# BLE_Connectivity.net
KiCad netlist of a schematic drawn in Altium Designer
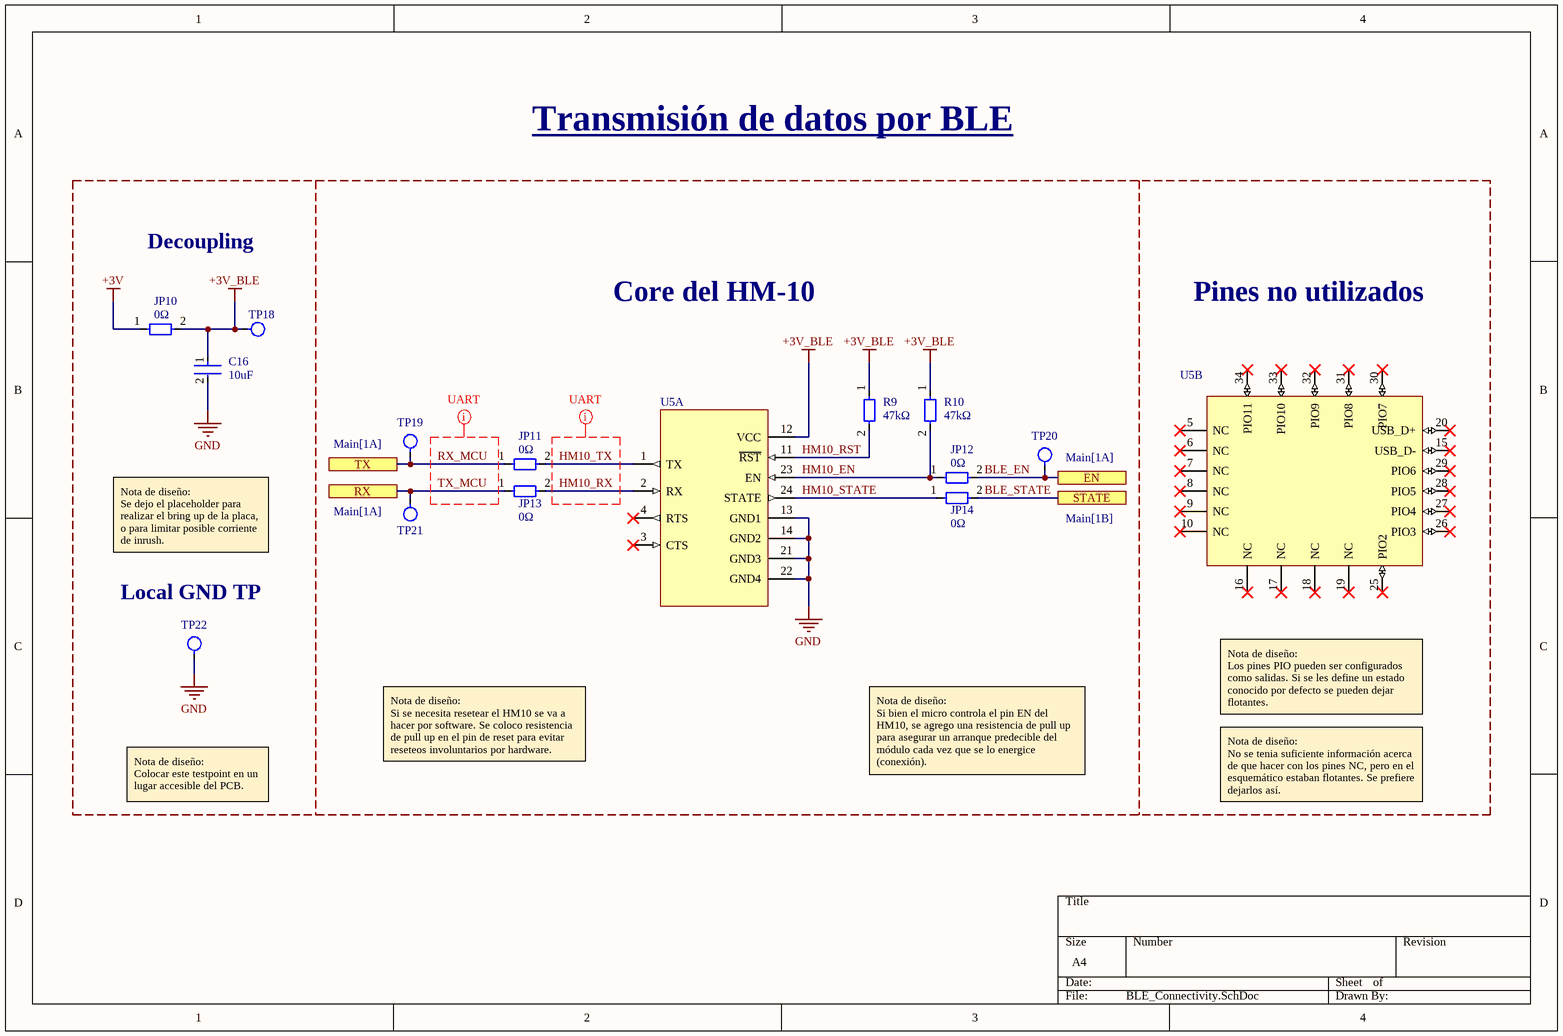
[diagram p0: BLE_Connectivity.SchDoc]

(export (version "E")
  (design (tool "Eeschema 10.0.6"))
  (components
    (comp (ref "C16")
      (value "10uF")
      (footprint "CAP_0603")
      (description "Cap 10 uF 10V X7R 0603")
      (fields (field (name "CAPACITANCE") "10uF") (field (name "TOLERANCE") "10%"))
      (libsource (lib "Passive_Components") (part "Generic C"))
    )
    (comp (ref "JP10")
      (value "0Ω")
      (footprint "RES_0R_0603")
      (description "Simbolo de jumper genérico")
      (fields (field (name "Comment") "Generic JP"))
      (libsource (lib "Passive_Components") (part "Generic JP"))
    )
    (comp (ref "JP11")
      (value "0Ω")
      (footprint "RES_0R_0603")
      (description "Simbolo de jumper genérico")
      (fields (field (name "Comment") "Generic JP"))
      (libsource (lib "Passive_Components") (part "Generic JP"))
    )
    (comp (ref "JP12")
      (value "0Ω")
      (footprint "RES_0R_0603")
      (description "Simbolo de jumper genérico")
      (fields (field (name "Comment") "Generic JP"))
      (libsource (lib "Passive_Components") (part "Generic JP"))
    )
    (comp (ref "JP13")
      (value "0Ω")
      (footprint "RES_0R_0603")
      (description "Simbolo de jumper genérico")
      (fields (field (name "Comment") "Generic JP"))
      (libsource (lib "Passive_Components") (part "Generic JP"))
    )
    (comp (ref "JP14")
      (value "0Ω")
      (footprint "RES_0R_0603")
      (description "Simbolo de jumper genérico")
      (fields (field (name "Comment") "Generic JP"))
      (libsource (lib "Passive_Components") (part "Generic JP"))
    )
    (comp (ref "R9")
      (value "47kΩ")
      (footprint "RES_0603")
      (description "RES  47k 1% 0603")
      (fields (field (name "Comment") "47k"))
      (libsource (lib "Passive_Components") (part "Generic R"))
    )
    (comp (ref "R10")
      (value "47kΩ")
      (footprint "RES_0603")
      (description "RES  47k 1% 0603")
      (fields (field (name "Comment") "47k"))
      (libsource (lib "Passive_Components") (part "Generic R"))
    )
    (comp (ref "TP18")
      (value "Testpoint SMD")
      (footprint "Testpoint_SMD")
      (description "Testpoint SMD de 1mm de diametro.")
      (libsource (lib "Connectors") (part "Testpoint_SMD"))
    )
    (comp (ref "TP19")
      (value "Testpoint SMD")
      (footprint "Testpoint_SMD")
      (description "Testpoint SMD de 1mm de diametro.")
      (libsource (lib "Connectors") (part "Testpoint_SMD"))
    )
    (comp (ref "TP20")
      (value "Testpoint SMD")
      (footprint "Testpoint_SMD")
      (description "Testpoint SMD de 1mm de diametro.")
      (libsource (lib "Connectors") (part "Testpoint_SMD"))
    )
    (comp (ref "TP21")
      (value "Testpoint SMD")
      (footprint "Testpoint_SMD")
      (description "Testpoint SMD de 1mm de diametro.")
      (libsource (lib "Connectors") (part "Testpoint_SMD"))
    )
    (comp (ref "TP22")
      (value "Testpoint SMD")
      (footprint "Testpoint_SMD")
      (description "Testpoint SMD de 1mm de diametro.")
      (libsource (lib "Connectors") (part "Testpoint_SMD"))
    )
    (comp (ref "U5")
      (value "HM10 BLE Module")
      (footprint "HM10_FOOTPRINT")
      (description "Modulo BLE HM10 con castellated pads.")
      (libsource (lib "Connectivity") (part "HM10"))
    )
  )
  (nets
    (net (code "1") (name "+3V") (class "Default")
      (node (ref "JP10") (pin "1") (pinfunction "1_1") (pintype "passive"))
    )
    (net (code "2") (name "+3V_BLE") (class "Default")
      (node (ref "C16") (pin "1") (pinfunction "1_1") (pintype "passive"))
      (node (ref "JP10") (pin "2") (pinfunction "2_2") (pintype "passive"))
      (node (ref "R10") (pin "1") (pinfunction "1_1") (pintype "passive"))
      (node (ref "R9") (pin "1") (pinfunction "1_1") (pintype "passive"))
      (node (ref "TP18") (pin "1") (pinfunction "1_1") (pintype "passive"))
      (node (ref "U5") (pin "12") (pinfunction "VCC_12") (pintype "power_in"))
    )
    (net (code "3") (name "/BLE_EN") (class "Default")
      (node (ref "JP12") (pin "2") (pinfunction "2_2") (pintype "passive"))
      (node (ref "TP20") (pin "1") (pinfunction "1_1") (pintype "passive"))
    )
    (net (code "4") (name "/BLE_STATE") (class "Default")
      (node (ref "JP14") (pin "2") (pinfunction "2_2") (pintype "passive"))
    )
    (net (code "5") (name "/HM10_EN") (class "Default")
      (node (ref "JP12") (pin "1") (pinfunction "1_1") (pintype "passive"))
      (node (ref "R10") (pin "2") (pinfunction "2_2") (pintype "passive"))
      (node (ref "U5") (pin "23") (pinfunction "EN_23") (pintype "input"))
    )
    (net (code "6") (name "/HM10_RST") (class "Default")
      (node (ref "R9") (pin "2") (pinfunction "2_2") (pintype "passive"))
      (node (ref "U5") (pin "11") (pinfunction "RST_11") (pintype "input"))
    )
    (net (code "7") (name "/HM10_RX") (class "Default")
      (node (ref "JP13") (pin "2") (pinfunction "2_2") (pintype "passive"))
      (node (ref "U5") (pin "2") (pinfunction "RX_2") (pintype "input"))
    )
    (net (code "8") (name "/HM10_STATE") (class "Default")
      (node (ref "JP14") (pin "1") (pinfunction "1_1") (pintype "passive"))
      (node (ref "U5") (pin "24") (pinfunction "STATE_24") (pintype "output"))
    )
    (net (code "9") (name "/HM10_TX") (class "Default")
      (node (ref "JP11") (pin "2") (pinfunction "2_2") (pintype "passive"))
      (node (ref "U5") (pin "1") (pinfunction "TX_1") (pintype "output"))
    )
    (net (code "10") (name "/RX_MCU") (class "Default")
      (node (ref "JP11") (pin "1") (pinfunction "1_1") (pintype "passive"))
      (node (ref "TP19") (pin "1") (pinfunction "1_1") (pintype "passive"))
    )
    (net (code "11") (name "/TX_MCU") (class "Default")
      (node (ref "JP13") (pin "1") (pinfunction "1_1") (pintype "passive"))
      (node (ref "TP21") (pin "1") (pinfunction "1_1") (pintype "passive"))
    )
    (net (code "12") (name "GND") (class "Default")
      (node (ref "C16") (pin "2") (pinfunction "2_2") (pintype "passive"))
      (node (ref "TP22") (pin "1") (pinfunction "1_1") (pintype "passive"))
      (node (ref "U5") (pin "13") (pinfunction "GND1_13") (pintype "power_in"))
      (node (ref "U5") (pin "14") (pinfunction "GND2_14") (pintype "power_in"))
      (node (ref "U5") (pin "21") (pinfunction "GND3_21") (pintype "power_in"))
      (node (ref "U5") (pin "22") (pinfunction "GND4_22") (pintype "power_in"))
    )
    (net (code "13") (name "unconnected-(U5A-CTS-Pad3)") (class "Default")
      (node (ref "U5") (pin "3") (pinfunction "CTS_3") (pintype "input+no_connect"))
    )
    (net (code "14") (name "unconnected-(U5A-RTS-Pad4)") (class "Default")
      (node (ref "U5") (pin "4") (pinfunction "RTS_4") (pintype "output+no_connect"))
    )
    (net (code "15") (name "unconnected-(U5B-NC-Pad5)") (class "Default")
      (node (ref "U5") (pin "5") (pinfunction "NC_5") (pintype "passive+no_connect"))
    )
    (net (code "16") (name "unconnected-(U5B-NC-Pad6)") (class "Default")
      (node (ref "U5") (pin "6") (pinfunction "NC_6") (pintype "passive+no_connect"))
    )
    (net (code "17") (name "unconnected-(U5B-NC-Pad7)") (class "Default")
      (node (ref "U5") (pin "7") (pinfunction "NC_7") (pintype "passive+no_connect"))
    )
    (net (code "18") (name "unconnected-(U5B-NC-Pad8)") (class "Default")
      (node (ref "U5") (pin "8") (pinfunction "NC_8") (pintype "passive+no_connect"))
    )
    (net (code "19") (name "unconnected-(U5B-NC-Pad9)") (class "Default")
      (node (ref "U5") (pin "9") (pinfunction "NC_9") (pintype "passive+no_connect"))
    )
    (net (code "20") (name "unconnected-(U5B-NC-Pad10)") (class "Default")
      (node (ref "U5") (pin "10") (pinfunction "NC_10") (pintype "passive+no_connect"))
    )
    (net (code "21") (name "unconnected-(U5B-NC-Pad16)") (class "Default")
      (node (ref "U5") (pin "16") (pinfunction "NC_16") (pintype "passive+no_connect"))
    )
    (net (code "22") (name "unconnected-(U5B-NC-Pad17)") (class "Default")
      (node (ref "U5") (pin "17") (pinfunction "NC_17") (pintype "passive+no_connect"))
    )
    (net (code "23") (name "unconnected-(U5B-NC-Pad18)") (class "Default")
      (node (ref "U5") (pin "18") (pinfunction "NC_18") (pintype "passive+no_connect"))
    )
    (net (code "24") (name "unconnected-(U5B-NC-Pad19)") (class "Default")
      (node (ref "U5") (pin "19") (pinfunction "NC_19") (pintype "passive+no_connect"))
    )
    (net (code "25") (name "unconnected-(U5B-PIO2-Pad25)") (class "Default")
      (node (ref "U5") (pin "25") (pinfunction "PIO2_25") (pintype "bidirectional+no_connect"))
    )
    (net (code "26") (name "unconnected-(U5B-PIO3-Pad26)") (class "Default")
      (node (ref "U5") (pin "26") (pinfunction "PIO3_26") (pintype "bidirectional+no_connect"))
    )
    (net (code "27") (name "unconnected-(U5B-PIO4-Pad27)") (class "Default")
      (node (ref "U5") (pin "27") (pinfunction "PIO4_27") (pintype "bidirectional+no_connect"))
    )
    (net (code "28") (name "unconnected-(U5B-PIO5-Pad28)") (class "Default")
      (node (ref "U5") (pin "28") (pinfunction "PIO5_28") (pintype "bidirectional+no_connect"))
    )
    (net (code "29") (name "unconnected-(U5B-PIO6-Pad29)") (class "Default")
      (node (ref "U5") (pin "29") (pinfunction "PIO6_29") (pintype "bidirectional+no_connect"))
    )
    (net (code "30") (name "unconnected-(U5B-PIO7-Pad30)") (class "Default")
      (node (ref "U5") (pin "30") (pinfunction "PIO7_30") (pintype "bidirectional+no_connect"))
    )
    (net (code "31") (name "unconnected-(U5B-PIO8-Pad31)") (class "Default")
      (node (ref "U5") (pin "31") (pinfunction "PIO8_31") (pintype "bidirectional+no_connect"))
    )
    (net (code "32") (name "unconnected-(U5B-PIO9-Pad32)") (class "Default")
      (node (ref "U5") (pin "32") (pinfunction "PIO9_32") (pintype "bidirectional+no_connect"))
    )
    (net (code "33") (name "unconnected-(U5B-PIO10-Pad33)") (class "Default")
      (node (ref "U5") (pin "33") (pinfunction "PIO10_33") (pintype "bidirectional+no_connect"))
    )
    (net (code "34") (name "unconnected-(U5B-PIO11-Pad34)") (class "Default")
      (node (ref "U5") (pin "34") (pinfunction "PIO11_34") (pintype "bidirectional+no_connect"))
    )
    (net (code "35") (name "unconnected-(U5B-USB_D+-Pad20)") (class "Default")
      (node (ref "U5") (pin "20") (pinfunction "USB_D+_20") (pintype "bidirectional+no_connect"))
    )
    (net (code "36") (name "unconnected-(U5B-USB_D--Pad15)") (class "Default")
      (node (ref "U5") (pin "15") (pinfunction "USB_D-_15") (pintype "bidirectional+no_connect"))
    )
  )
)
